# Arduino_Euclidean_Board_Controls_top.net
KiCad netlist of a schematic drawn in EAGLE
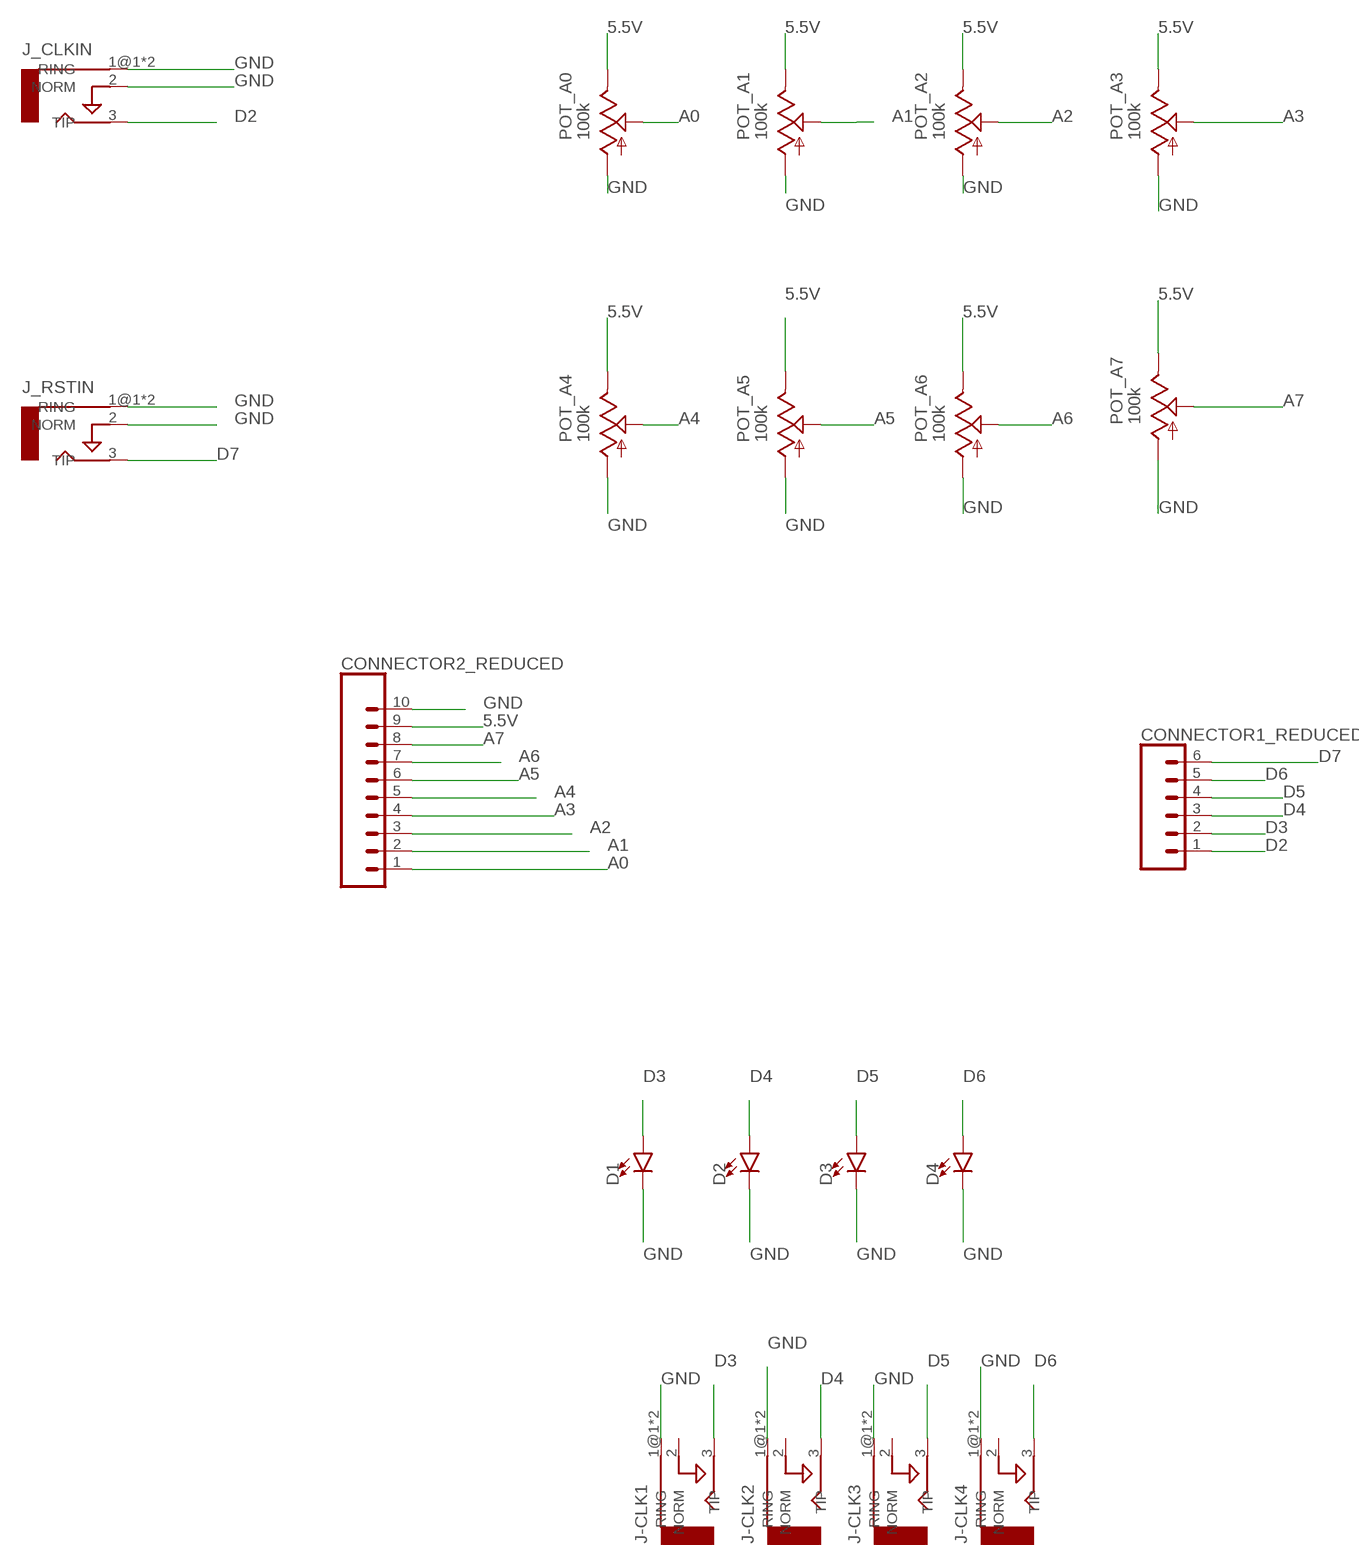
[diagram p0: schematic, sheet 1]

(export (version "E")
  (design (tool "Eeschema 10.0.6"))
  (components
    (comp (ref "CONNECTOR1_REDUCED")
      (value "CONN_06LONGPADS")
      (footprint "eagle-import:1X06_LONGPADS")
      (libsource (lib "eagle-import") (part "CONN_06LONGPADS"))
    )
    (comp (ref "CONNECTOR2_REDUCED")
      (value "CONN_10_LONGPADS10_LONGPADS")
      (footprint "eagle-import:1X10_LONGPADS")
      (libsource (lib "eagle-import") (part "CONN_10_LONGPADS10_LONGPADS"))
    )
    (comp (ref "D1")
      (value "LED-3MM-NO_SILK")
      (footprint "eagle-import:LED_3MM-NS")
      (libsource (lib "eagle-import") (part "LED-3MM-NO_SILK"))
    )
    (comp (ref "D2")
      (value "LED-3MM-NO_SILK")
      (footprint "eagle-import:LED_3MM-NS")
      (libsource (lib "eagle-import") (part "LED-3MM-NO_SILK"))
    )
    (comp (ref "D3")
      (value "LED-3MM-NO_SILK")
      (footprint "eagle-import:LED_3MM-NS")
      (libsource (lib "eagle-import") (part "LED-3MM-NO_SILK"))
    )
    (comp (ref "D4")
      (value "LED-3MM-NO_SILK")
      (footprint "eagle-import:LED_3MM-NS")
      (libsource (lib "eagle-import") (part "LED-3MM-NO_SILK"))
    )
    (comp (ref "J-CLK1")
      (value "AUDIO-JACKERTHENVAR")
      (footprint "eagle-import:ERTHENVAR-JACK")
      (libsource (lib "eagle-import") (part "AUDIO-JACKERTHENVAR"))
    )
    (comp (ref "J-CLK2")
      (value "AUDIO-JACKERTHENVAR")
      (footprint "eagle-import:ERTHENVAR-JACK")
      (libsource (lib "eagle-import") (part "AUDIO-JACKERTHENVAR"))
    )
    (comp (ref "J-CLK3")
      (value "AUDIO-JACKERTHENVAR")
      (footprint "eagle-import:ERTHENVAR-JACK")
      (libsource (lib "eagle-import") (part "AUDIO-JACKERTHENVAR"))
    )
    (comp (ref "J-CLK4")
      (value "AUDIO-JACKERTHENVAR")
      (footprint "eagle-import:ERTHENVAR-JACK")
      (libsource (lib "eagle-import") (part "AUDIO-JACKERTHENVAR"))
    )
    (comp (ref "J_CLKIN")
      (value "AUDIO-JACKERTHENVAR")
      (footprint "eagle-import:ERTHENVAR-JACK")
      (libsource (lib "eagle-import") (part "AUDIO-JACKERTHENVAR"))
    )
    (comp (ref "J_RSTIN")
      (value "AUDIO-JACKERTHENVAR")
      (footprint "eagle-import:ERTHENVAR-JACK")
      (libsource (lib "eagle-import") (part "AUDIO-JACKERTHENVAR"))
    )
    (comp (ref "POT_A0")
      (value "100k")
      (footprint "eagle-import:9MM_SNAP-IN_POT")
      (libsource (lib "eagle-import") (part "9MM_SNAP-IN_POT_"))
    )
    (comp (ref "POT_A1")
      (value "100k")
      (footprint "eagle-import:9MM_SNAP-IN_POT")
      (libsource (lib "eagle-import") (part "9MM_SNAP-IN_POT_"))
    )
    (comp (ref "POT_A2")
      (value "100k")
      (footprint "eagle-import:9MM_SNAP-IN_POT")
      (libsource (lib "eagle-import") (part "9MM_SNAP-IN_POT_"))
    )
    (comp (ref "POT_A3")
      (value "100k")
      (footprint "eagle-import:9MM_SNAP-IN_POT")
      (libsource (lib "eagle-import") (part "9MM_SNAP-IN_POT_"))
    )
    (comp (ref "POT_A4")
      (value "100k")
      (footprint "eagle-import:9MM_SNAP-IN_POT")
      (libsource (lib "eagle-import") (part "9MM_SNAP-IN_POT_"))
    )
    (comp (ref "POT_A5")
      (value "100k")
      (footprint "eagle-import:9MM_SNAP-IN_POT")
      (libsource (lib "eagle-import") (part "9MM_SNAP-IN_POT_"))
    )
    (comp (ref "POT_A6")
      (value "100k")
      (footprint "eagle-import:9MM_SNAP-IN_POT")
      (libsource (lib "eagle-import") (part "9MM_SNAP-IN_POT_"))
    )
    (comp (ref "POT_A7")
      (value "100k")
      (footprint "eagle-import:9MM_SNAP-IN_POT")
      (libsource (lib "eagle-import") (part "9MM_SNAP-IN_POT_"))
    )
  )
  (nets
    (net (code "1") (name "/5.5V") (class "Default")
      (node (ref "CONNECTOR2_REDUCED") (pin "9") (pinfunction "9_9") (pintype "passive"))
      (node (ref "POT_A0") (pin "3") (pinfunction "E_3") (pintype "passive"))
      (node (ref "POT_A1") (pin "3") (pinfunction "E_3") (pintype "passive"))
      (node (ref "POT_A2") (pin "3") (pinfunction "E_3") (pintype "passive"))
      (node (ref "POT_A3") (pin "3") (pinfunction "E_3") (pintype "passive"))
      (node (ref "POT_A4") (pin "3") (pinfunction "E_3") (pintype "passive"))
      (node (ref "POT_A5") (pin "3") (pinfunction "E_3") (pintype "passive"))
      (node (ref "POT_A6") (pin "3") (pinfunction "E_3") (pintype "passive"))
      (node (ref "POT_A7") (pin "3") (pinfunction "E_3") (pintype "passive"))
    )
    (net (code "2") (name "/A0") (class "Default")
      (node (ref "CONNECTOR2_REDUCED") (pin "1") (pinfunction "1_1") (pintype "passive"))
      (node (ref "POT_A0") (pin "2") (pinfunction "S_2") (pintype "passive"))
    )
    (net (code "3") (name "/A1") (class "Default")
      (node (ref "CONNECTOR2_REDUCED") (pin "2") (pinfunction "2_2") (pintype "passive"))
      (node (ref "POT_A1") (pin "2") (pinfunction "S_2") (pintype "passive"))
    )
    (net (code "4") (name "/A2") (class "Default")
      (node (ref "CONNECTOR2_REDUCED") (pin "3") (pinfunction "3_3") (pintype "passive"))
      (node (ref "POT_A2") (pin "2") (pinfunction "S_2") (pintype "passive"))
    )
    (net (code "5") (name "/A3") (class "Default")
      (node (ref "CONNECTOR2_REDUCED") (pin "4") (pinfunction "4_4") (pintype "passive"))
      (node (ref "POT_A3") (pin "2") (pinfunction "S_2") (pintype "passive"))
    )
    (net (code "6") (name "/A4") (class "Default")
      (node (ref "CONNECTOR2_REDUCED") (pin "5") (pinfunction "5_5") (pintype "passive"))
      (node (ref "POT_A4") (pin "2") (pinfunction "S_2") (pintype "passive"))
    )
    (net (code "7") (name "/A5") (class "Default")
      (node (ref "CONNECTOR2_REDUCED") (pin "6") (pinfunction "6_6") (pintype "passive"))
      (node (ref "POT_A5") (pin "2") (pinfunction "S_2") (pintype "passive"))
    )
    (net (code "8") (name "/A6") (class "Default")
      (node (ref "CONNECTOR2_REDUCED") (pin "7") (pinfunction "7_7") (pintype "passive"))
      (node (ref "POT_A6") (pin "2") (pinfunction "S_2") (pintype "passive"))
    )
    (net (code "9") (name "/A7") (class "Default")
      (node (ref "CONNECTOR2_REDUCED") (pin "8") (pinfunction "8_8") (pintype "passive"))
      (node (ref "POT_A7") (pin "2") (pinfunction "S_2") (pintype "passive"))
    )
    (net (code "10") (name "/D2") (class "Default")
      (node (ref "CONNECTOR1_REDUCED") (pin "1") (pinfunction "1_1") (pintype "passive"))
      (node (ref "J_CLKIN") (pin "3") (pinfunction "TIP_3") (pintype "bidirectional"))
    )
    (net (code "11") (name "/D3") (class "Default")
      (node (ref "CONNECTOR1_REDUCED") (pin "2") (pinfunction "2_2") (pintype "passive"))
      (node (ref "D1") (pin "A") (pinfunction "A_A") (pintype "passive"))
      (node (ref "J-CLK1") (pin "3") (pinfunction "TIP_3") (pintype "bidirectional"))
    )
    (net (code "12") (name "/D4") (class "Default")
      (node (ref "CONNECTOR1_REDUCED") (pin "3") (pinfunction "3_3") (pintype "passive"))
      (node (ref "D2") (pin "A") (pinfunction "A_A") (pintype "passive"))
      (node (ref "J-CLK2") (pin "3") (pinfunction "TIP_3") (pintype "bidirectional"))
    )
    (net (code "13") (name "/D5") (class "Default")
      (node (ref "CONNECTOR1_REDUCED") (pin "4") (pinfunction "4_4") (pintype "passive"))
      (node (ref "D3") (pin "A") (pinfunction "A_A") (pintype "passive"))
      (node (ref "J-CLK3") (pin "3") (pinfunction "TIP_3") (pintype "bidirectional"))
    )
    (net (code "14") (name "/D6") (class "Default")
      (node (ref "CONNECTOR1_REDUCED") (pin "5") (pinfunction "5_5") (pintype "passive"))
      (node (ref "D4") (pin "A") (pinfunction "A_A") (pintype "passive"))
      (node (ref "J-CLK4") (pin "3") (pinfunction "TIP_3") (pintype "bidirectional"))
    )
    (net (code "15") (name "/D7") (class "Default")
      (node (ref "CONNECTOR1_REDUCED") (pin "6") (pinfunction "6_6") (pintype "passive"))
      (node (ref "J_RSTIN") (pin "3") (pinfunction "TIP_3") (pintype "bidirectional"))
    )
    (net (code "16") (name "/GND") (class "Default")
      (node (ref "CONNECTOR2_REDUCED") (pin "10") (pinfunction "10_10") (pintype "passive"))
      (node (ref "D1") (pin "K") (pinfunction "C_K") (pintype "passive"))
      (node (ref "D2") (pin "K") (pinfunction "C_K") (pintype "passive"))
      (node (ref "D3") (pin "K") (pinfunction "C_K") (pintype "passive"))
      (node (ref "D4") (pin "K") (pinfunction "C_K") (pintype "passive"))
      (node (ref "J-CLK1") (pin "1@1") (pinfunction "RING_1@1") (pintype "bidirectional"))
      (node (ref "J-CLK1") (pin "1@2") (pinfunction "RING_1@2") (pintype "bidirectional"))
      (node (ref "J-CLK2") (pin "1@1") (pinfunction "RING_1@1") (pintype "bidirectional"))
      (node (ref "J-CLK2") (pin "1@2") (pinfunction "RING_1@2") (pintype "bidirectional"))
      (node (ref "J-CLK3") (pin "1@1") (pinfunction "RING_1@1") (pintype "bidirectional"))
      (node (ref "J-CLK3") (pin "1@2") (pinfunction "RING_1@2") (pintype "bidirectional"))
      (node (ref "J-CLK4") (pin "1@1") (pinfunction "RING_1@1") (pintype "bidirectional"))
      (node (ref "J-CLK4") (pin "1@2") (pinfunction "RING_1@2") (pintype "bidirectional"))
      (node (ref "J_CLKIN") (pin "1@1") (pinfunction "RING_1@1") (pintype "bidirectional"))
      (node (ref "J_CLKIN") (pin "1@2") (pinfunction "RING_1@2") (pintype "bidirectional"))
      (node (ref "J_CLKIN") (pin "2") (pinfunction "NORM_2") (pintype "bidirectional"))
      (node (ref "J_RSTIN") (pin "1@1") (pinfunction "RING_1@1") (pintype "bidirectional"))
      (node (ref "J_RSTIN") (pin "1@2") (pinfunction "RING_1@2") (pintype "bidirectional"))
      (node (ref "J_RSTIN") (pin "2") (pinfunction "NORM_2") (pintype "bidirectional"))
      (node (ref "POT_A0") (pin "1") (pinfunction "A_1") (pintype "passive"))
      (node (ref "POT_A1") (pin "1") (pinfunction "A_1") (pintype "passive"))
      (node (ref "POT_A2") (pin "1") (pinfunction "A_1") (pintype "passive"))
      (node (ref "POT_A3") (pin "1") (pinfunction "A_1") (pintype "passive"))
      (node (ref "POT_A4") (pin "1") (pinfunction "A_1") (pintype "passive"))
      (node (ref "POT_A5") (pin "1") (pinfunction "A_1") (pintype "passive"))
      (node (ref "POT_A6") (pin "1") (pinfunction "A_1") (pintype "passive"))
      (node (ref "POT_A7") (pin "1") (pinfunction "A_1") (pintype "passive"))
    )
    (net (code "17") (name "unconnected-(J-CLK1-NORM-Pad2)") (class "Default")
      (node (ref "J-CLK1") (pin "2") (pinfunction "NORM_2") (pintype "bidirectional"))
    )
    (net (code "18") (name "unconnected-(J-CLK2-NORM-Pad2)") (class "Default")
      (node (ref "J-CLK2") (pin "2") (pinfunction "NORM_2") (pintype "bidirectional"))
    )
    (net (code "19") (name "unconnected-(J-CLK3-NORM-Pad2)") (class "Default")
      (node (ref "J-CLK3") (pin "2") (pinfunction "NORM_2") (pintype "bidirectional"))
    )
    (net (code "20") (name "unconnected-(J-CLK4-NORM-Pad2)") (class "Default")
      (node (ref "J-CLK4") (pin "2") (pinfunction "NORM_2") (pintype "bidirectional"))
    )
  )
)
